# controller.net
KiCad netlist of a schematic drawn in EAGLE
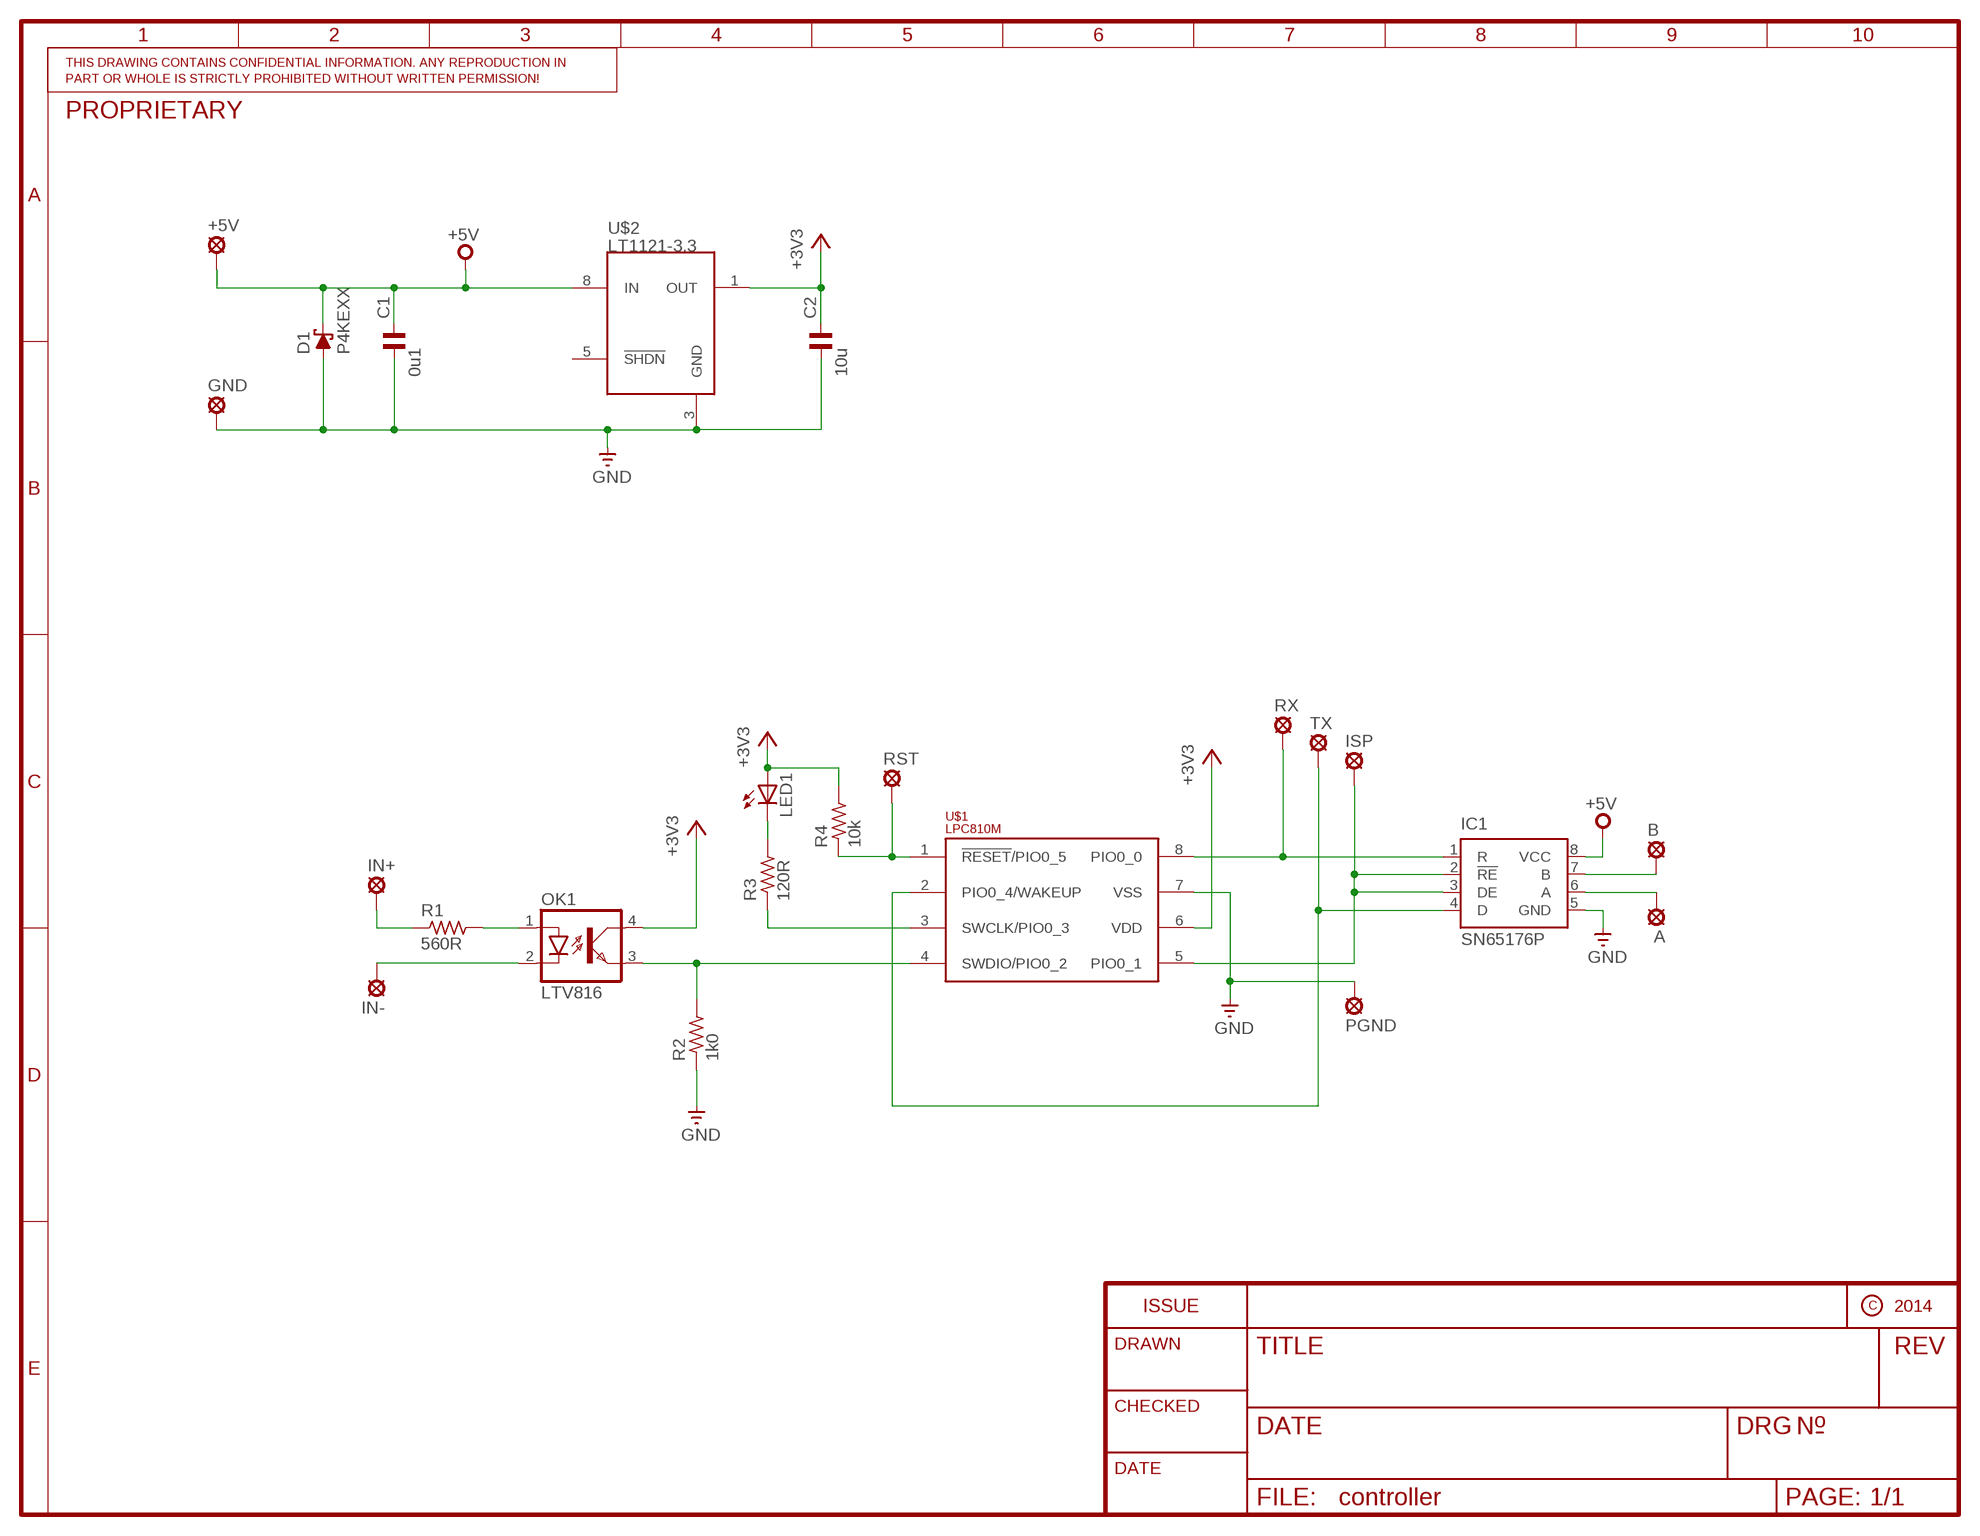
[diagram p0: schematic, sheet 1]

(export (version "E")
  (design (tool "Eeschema 10.0.6"))
  (components
    (comp (ref "+5V")
      (value "SE14")
      (footprint "eagle-import:SE14")
      (libsource (lib "eagle-import") (part "SE14"))
    )
    (comp (ref "A")
      (value "SE14")
      (footprint "eagle-import:SE14")
      (libsource (lib "eagle-import") (part "SE14"))
    )
    (comp (ref "B")
      (value "SE14")
      (footprint "eagle-import:SE14")
      (libsource (lib "eagle-import") (part "SE14"))
    )
    (comp (ref "C1")
      (value "0u1")
      (footprint "eagle-import:C050-024X044")
      (libsource (lib "eagle-import") (part "C-EU050-024X044"))
    )
    (comp (ref "C2")
      (value "10u")
      (footprint "eagle-import:C050-024X044")
      (libsource (lib "eagle-import") (part "C-EU050-024X044"))
    )
    (comp (ref "D1")
      (value "P4KEXX")
      (footprint "eagle-import:DO41-10")
      (libsource (lib "eagle-import") (part "P4KEXX"))
    )
    (comp (ref "GND")
      (value "SE14")
      (footprint "eagle-import:SE14")
      (libsource (lib "eagle-import") (part "SE14"))
    )
    (comp (ref "IC1")
      (value "SN65176P")
      (footprint "eagle-import:DIL08")
      (fields (field (name "MF") "TEXAS INSTRUMENTS") (field (name "MPN") "SN65176BP"))
      (libsource (lib "eagle-import") (part "SN65176P"))
    )
    (comp (ref "IN+")
      (value "SE14")
      (footprint "eagle-import:SE14")
      (libsource (lib "eagle-import") (part "SE14"))
    )
    (comp (ref "IN-")
      (value "SE14")
      (footprint "eagle-import:SE14")
      (libsource (lib "eagle-import") (part "SE14"))
    )
    (comp (ref "ISP")
      (value "SE14")
      (footprint "eagle-import:SE14")
      (libsource (lib "eagle-import") (part "SE14"))
    )
    (comp (ref "LED1")
      (value "LED-3MM-NO_SILK")
      (footprint "eagle-import:LED3MM-NS")
      (libsource (lib "eagle-import") (part "LED-3MM-NO_SILK"))
    )
    (comp (ref "OK1")
      (value "LTV816")
      (footprint "eagle-import:DIL04")
      (libsource (lib "eagle-import") (part "LTV816"))
    )
    (comp (ref "PGND")
      (value "SE14")
      (footprint "eagle-import:SE14")
      (libsource (lib "eagle-import") (part "SE14"))
    )
    (comp (ref "R1")
      (value "560R")
      (footprint "eagle-import:0207_10B")
      (libsource (lib "eagle-import") (part "R-EU_0207/10B"))
    )
    (comp (ref "R2")
      (value "1k0")
      (footprint "eagle-import:0207_10B")
      (libsource (lib "eagle-import") (part "R-EU_0207/10B"))
    )
    (comp (ref "R3")
      (value "120R")
      (footprint "eagle-import:0207_10B")
      (libsource (lib "eagle-import") (part "R-EU_0207/10B"))
    )
    (comp (ref "R4")
      (value "10k")
      (footprint "eagle-import:0207_10B")
      (libsource (lib "eagle-import") (part "R-EU_0207/10B"))
    )
    (comp (ref "RST")
      (value "SE14")
      (footprint "eagle-import:SE14")
      (libsource (lib "eagle-import") (part "SE14"))
    )
    (comp (ref "RX")
      (value "SE14")
      (footprint "eagle-import:SE14")
      (libsource (lib "eagle-import") (part "SE14"))
    )
    (comp (ref "TX")
      (value "SE14")
      (footprint "eagle-import:SE14")
      (libsource (lib "eagle-import") (part "SE14"))
    )
    (comp (ref "U$1")
      (value "LPC810M")
      (footprint "eagle-import:DIL08")
      (libsource (lib "eagle-import") (part "LPC810M"))
    )
    (comp (ref "U$2")
      (value "LT1121-3.3")
      (footprint "eagle-import:DIL08")
      (libsource (lib "eagle-import") (part "LT1121-3.3"))
    )
  )
  (nets
    (net (code "1") (name "+3V3") (class "Default")
      (node (ref "C2") (pin "1") (pinfunction "1_1") (pintype "passive"))
      (node (ref "LED1") (pin "A") (pinfunction "A_A") (pintype "passive"))
      (node (ref "OK1") (pin "4") (pinfunction "COL_4") (pintype "passive"))
      (node (ref "R4") (pin "2") (pinfunction "2_2") (pintype "passive"))
      (node (ref "U$1") (pin "6") (pinfunction "VDD_6") (pintype "bidirectional"))
      (node (ref "U$2") (pin "1") (pinfunction "OUT_1") (pintype "bidirectional"))
    )
    (net (code "2") (name "+5V") (class "Default")
      (node (ref "+5V") (pin "MP") (pinfunction "MP_MP") (pintype "passive"))
      (node (ref "C1") (pin "1") (pinfunction "1_1") (pintype "passive"))
      (node (ref "D1") (pin "C") (pinfunction "C_C") (pintype "passive"))
      (node (ref "IC1") (pin "8") (pinfunction "VCC_8") (pintype "input"))
      (node (ref "U$2") (pin "8") (pinfunction "IN_8") (pintype "bidirectional"))
    )
    (net (code "3") (name "GND") (class "Default")
      (node (ref "C1") (pin "2") (pinfunction "2_2") (pintype "passive"))
      (node (ref "C2") (pin "2") (pinfunction "2_2") (pintype "passive"))
      (node (ref "D1") (pin "A") (pinfunction "A_A") (pintype "passive"))
      (node (ref "GND") (pin "MP") (pinfunction "MP_MP") (pintype "passive"))
      (node (ref "IC1") (pin "5") (pinfunction "GND_5") (pintype "input"))
      (node (ref "PGND") (pin "MP") (pinfunction "MP_MP") (pintype "passive"))
      (node (ref "R2") (pin "1") (pinfunction "1_1") (pintype "passive"))
      (node (ref "U$1") (pin "7") (pinfunction "VSS_7") (pintype "bidirectional"))
      (node (ref "U$2") (pin "3") (pinfunction "GND_3") (pintype "bidirectional"))
    )
    (net (code "4") (name "Net-(IC1-A)") (class "Default")
      (node (ref "A") (pin "MP") (pinfunction "MP_MP") (pintype "passive"))
      (node (ref "IC1") (pin "6") (pinfunction "A_6") (pintype "input"))
    )
    (net (code "5") (name "Net-(IC1-B)") (class "Default")
      (node (ref "B") (pin "MP") (pinfunction "MP_MP") (pintype "passive"))
      (node (ref "IC1") (pin "7") (pinfunction "B_7") (pintype "input"))
    )
    (net (code "6") (name "Net-(IC1-D)") (class "Default")
      (node (ref "IC1") (pin "4") (pinfunction "D_4") (pintype "input"))
      (node (ref "TX") (pin "MP") (pinfunction "MP_MP") (pintype "passive"))
      (node (ref "U$1") (pin "2") (pinfunction "PIO0_4/WAKEUP_2") (pintype "bidirectional"))
    )
    (net (code "7") (name "Net-(IC1-DE)") (class "Default")
      (node (ref "IC1") (pin "2") (pinfunction "~{RE}_2") (pintype "input"))
      (node (ref "IC1") (pin "3") (pinfunction "DE_3") (pintype "input"))
      (node (ref "ISP") (pin "MP") (pinfunction "MP_MP") (pintype "passive"))
      (node (ref "U$1") (pin "5") (pinfunction "PIO0_1_5") (pintype "bidirectional"))
    )
    (net (code "8") (name "Net-(IC1-R)") (class "Default")
      (node (ref "IC1") (pin "1") (pinfunction "R_1") (pintype "input"))
      (node (ref "RX") (pin "MP") (pinfunction "MP_MP") (pintype "passive"))
      (node (ref "U$1") (pin "8") (pinfunction "PIO0_0_8") (pintype "bidirectional"))
    )
    (net (code "9") (name "Net-(IN+-PadMP)") (class "Default")
      (node (ref "IN+") (pin "MP") (pinfunction "MP_MP") (pintype "passive"))
      (node (ref "R1") (pin "1") (pinfunction "1_1") (pintype "passive"))
    )
    (net (code "10") (name "Net-(LED1-C)") (class "Default")
      (node (ref "LED1") (pin "K") (pinfunction "C_K") (pintype "passive"))
      (node (ref "R3") (pin "2") (pinfunction "2_2") (pintype "passive"))
    )
    (net (code "11") (name "Net-(OK1-A)") (class "Default")
      (node (ref "OK1") (pin "1") (pinfunction "A_1") (pintype "passive"))
      (node (ref "R1") (pin "2") (pinfunction "2_2") (pintype "passive"))
    )
    (net (code "12") (name "Net-(OK1-C)") (class "Default")
      (node (ref "IN-") (pin "MP") (pinfunction "MP_MP") (pintype "passive"))
      (node (ref "OK1") (pin "2") (pinfunction "C_2") (pintype "passive"))
    )
    (net (code "13") (name "Net-(OK1-EMIT)") (class "Default")
      (node (ref "OK1") (pin "3") (pinfunction "EMIT_3") (pintype "passive"))
      (node (ref "R2") (pin "2") (pinfunction "2_2") (pintype "passive"))
      (node (ref "U$1") (pin "4") (pinfunction "SWDIO/PIO0_2_4") (pintype "bidirectional"))
    )
    (net (code "14") (name "Net-(U$1-SWCLK{slash}PIO0_3)") (class "Default")
      (node (ref "R3") (pin "1") (pinfunction "1_1") (pintype "passive"))
      (node (ref "U$1") (pin "3") (pinfunction "SWCLK/PIO0_3_3") (pintype "bidirectional"))
    )
    (net (code "15") (name "Net-(U$1-~{RESET}{slash}PIO0_5)") (class "Default")
      (node (ref "R4") (pin "1") (pinfunction "1_1") (pintype "passive"))
      (node (ref "RST") (pin "MP") (pinfunction "MP_MP") (pintype "passive"))
      (node (ref "U$1") (pin "1") (pinfunction "~{RESET}/PIO0_5_1") (pintype "bidirectional"))
    )
    (net (code "16") (name "unconnected-(U$2-~{SHDN}-Pad5)") (class "Default")
      (node (ref "U$2") (pin "5") (pinfunction "~{SHDN}_5") (pintype "bidirectional"))
    )
  )
)
